# design.net
KiCad netlist of a schematic drawn in Altium Designer
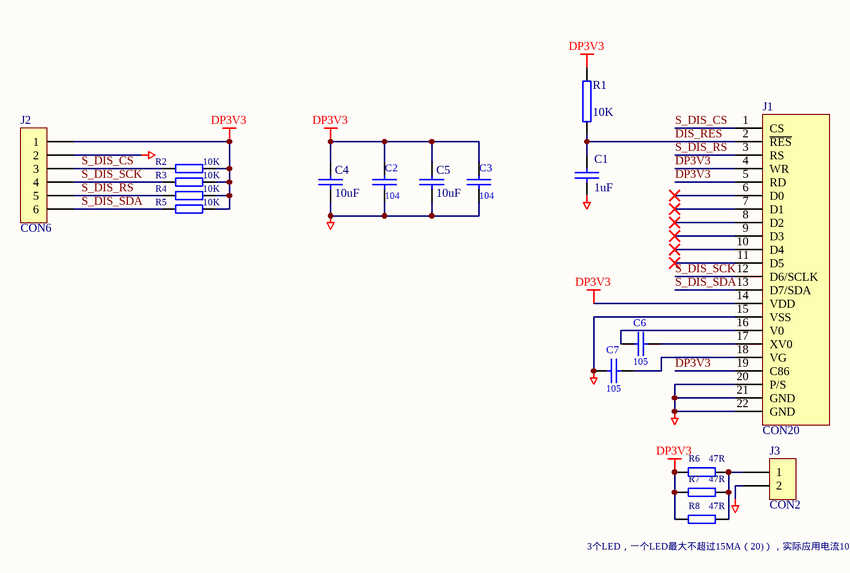
[diagram p0: 迷你随车充液晶显示板.SchDoc]

(export (version "E")
  (design (tool "Eeschema 10.0.6"))
  (components
    (comp (ref "C1")
      (value "1uF")
      (footprint "0603C")
      (description "0603贴片电容/50V/0.1uF/±10%/X7R")
      (libsource (lib "*") (part "CAP1"))
    )
    (comp (ref "C2")
      (value "104")
      (footprint "0603C")
      (description "Capacitor")
      (libsource (lib "*") (part "CAP"))
    )
    (comp (ref "C3")
      (value "104")
      (footprint "0603C")
      (description "Capacitor")
      (libsource (lib "*") (part "CAP"))
    )
    (comp (ref "C4") (value "10uF") (footprint "0805C") (libsource (lib "*") (part "CAP1")))
    (comp (ref "C5") (value "10uF") (footprint "0805C") (libsource (lib "*") (part "CAP1")))
    (comp (ref "C6")
      (value "105")
      (footprint "0603C")
      (description "Capacitor")
      (libsource (lib "*") (part "CAP"))
    )
    (comp (ref "C7")
      (value "105")
      (footprint "0603C")
      (description "Capacitor")
      (libsource (lib "*") (part "CAP"))
    )
    (comp (ref "J1")
      (value "CON20")
      (footprint "FPC20-0.5mm")
      (description "Connector")
      (libsource (lib "SCH") (part "CON20"))
    )
    (comp (ref "J2")
      (value "CON6")
      (footprint "CON06_2.54")
      (description "Connector")
      (libsource (lib "*") (part "CON6"))
    )
    (comp (ref "J3")
      (value "CON2")
      (footprint "JXL12864G-1504")
      (description "Connector")
      (libsource (lib "SCH") (part "CON2"))
    )
    (comp (ref "R1")
      (value "10K")
      (footprint "0603R")
      (description "0603贴片电阻/10K/0.1W/±5%")
      (libsource (lib "*") (part "RES1"))
    )
    (comp (ref "R2")
      (value "10K")
      (footprint "0603R")
      (description "RES")
      (libsource (lib "*") (part "RES-1"))
    )
    (comp (ref "R3")
      (value "10K")
      (footprint "0603R")
      (description "RES")
      (libsource (lib "*") (part "RES-1"))
    )
    (comp (ref "R4")
      (value "10K")
      (footprint "0603R")
      (description "RES")
      (libsource (lib "*") (part "RES-1"))
    )
    (comp (ref "R5")
      (value "10K")
      (footprint "0603R")
      (description "RES")
      (libsource (lib "*") (part "RES-1"))
    )
    (comp (ref "R6")
      (value "47R")
      (footprint "0603R")
      (description "RES")
      (libsource (lib "*") (part "RES-1"))
    )
    (comp (ref "R7")
      (value "47R")
      (footprint "0603R")
      (description "RES")
      (libsource (lib "*") (part "RES-1"))
    )
    (comp (ref "R8")
      (value "47R")
      (footprint "0603R")
      (description "RES")
      (libsource (lib "*") (part "RES-1"))
    )
  )
  (nets
    (net (code "1") (name "/DIS_RES") (class "Default")
      (node (ref "C1") (pin "2") (pinfunction "2_2") (pintype "passive"))
      (node (ref "J1") (pin "2") (pinfunction "~{RES}_2") (pintype "passive"))
      (node (ref "R1") (pin "2") (pinfunction "2_2") (pintype "passive"))
    )
    (net (code "2") (name "/S_DIS_CS") (class "Default")
      (node (ref "J1") (pin "1") (pinfunction "CS_1") (pintype "passive"))
      (node (ref "J2") (pin "3") (pinfunction "3_3") (pintype "passive"))
      (node (ref "R2") (pin "1") (pintype "passive"))
    )
    (net (code "3") (name "/S_DIS_RS") (class "Default")
      (node (ref "J1") (pin "3") (pinfunction "RS_3") (pintype "passive"))
      (node (ref "J2") (pin "5") (pinfunction "5_5") (pintype "passive"))
      (node (ref "R4") (pin "1") (pintype "passive"))
    )
    (net (code "4") (name "/S_DIS_SCK") (class "Default")
      (node (ref "J1") (pin "12") (pinfunction "D6/SCLK_12") (pintype "passive"))
      (node (ref "J2") (pin "4") (pinfunction "4_4") (pintype "passive"))
      (node (ref "R3") (pin "1") (pintype "passive"))
    )
    (net (code "5") (name "/S_DIS_SDA") (class "Default")
      (node (ref "J1") (pin "13") (pinfunction "D7/SDA_13") (pintype "passive"))
      (node (ref "J2") (pin "6") (pinfunction "6_6") (pintype "passive"))
      (node (ref "R5") (pin "1") (pintype "passive"))
    )
    (net (code "6") (name "DGND") (class "Default")
      (node (ref "C1") (pin "1") (pinfunction "1_1") (pintype "passive"))
      (node (ref "C2") (pin "1") (pintype "passive"))
      (node (ref "C3") (pin "1") (pintype "passive"))
      (node (ref "C4") (pin "2") (pinfunction "2_2") (pintype "passive"))
      (node (ref "C5") (pin "2") (pinfunction "2_2") (pintype "passive"))
      (node (ref "C7") (pin "2") (pintype "passive"))
      (node (ref "J1") (pin "15") (pinfunction "VSS_15") (pintype "passive"))
      (node (ref "J1") (pin "20") (pinfunction "P/S_20") (pintype "passive"))
      (node (ref "J1") (pin "21") (pinfunction "GND_21") (pintype "passive"))
      (node (ref "J1") (pin "22") (pinfunction "GND_22") (pintype "passive"))
      (node (ref "J2") (pin "2") (pinfunction "2_2") (pintype "passive"))
      (node (ref "J3") (pin "2") (pinfunction "2_2") (pintype "passive"))
    )
    (net (code "7") (name "DP3V3") (class "Default")
      (node (ref "C2") (pin "2") (pintype "passive"))
      (node (ref "C3") (pin "2") (pintype "passive"))
      (node (ref "C4") (pin "1") (pinfunction "1_1") (pintype "passive"))
      (node (ref "C5") (pin "1") (pinfunction "1_1") (pintype "passive"))
      (node (ref "J1") (pin "14") (pinfunction "VDD_14") (pintype "passive"))
      (node (ref "J1") (pin "19") (pinfunction "C86_19") (pintype "passive"))
      (node (ref "J1") (pin "4") (pinfunction "WR_4") (pintype "passive"))
      (node (ref "J1") (pin "5") (pinfunction "RD_5") (pintype "passive"))
      (node (ref "J2") (pin "1") (pinfunction "1_1") (pintype "passive"))
      (node (ref "R1") (pin "1") (pinfunction "1_1") (pintype "passive"))
      (node (ref "R2") (pin "2") (pintype "passive"))
      (node (ref "R3") (pin "2") (pintype "passive"))
      (node (ref "R4") (pin "2") (pintype "passive"))
      (node (ref "R5") (pin "2") (pintype "passive"))
      (node (ref "R6") (pin "1") (pintype "passive"))
      (node (ref "R7") (pin "1") (pintype "passive"))
      (node (ref "R8") (pin "1") (pintype "passive"))
    )
    (net (code "8") (name "Net-(J1-V0)") (class "Default")
      (node (ref "C6") (pin "2") (pintype "passive"))
      (node (ref "J1") (pin "16") (pinfunction "V0_16") (pintype "passive"))
    )
    (net (code "9") (name "Net-(J1-VG)") (class "Default")
      (node (ref "C7") (pin "1") (pintype "passive"))
      (node (ref "J1") (pin "18") (pinfunction "VG_18") (pintype "passive"))
    )
    (net (code "10") (name "Net-(J1-XV0)") (class "Default")
      (node (ref "C6") (pin "1") (pintype "passive"))
      (node (ref "J1") (pin "17") (pinfunction "XV0_17") (pintype "passive"))
    )
    (net (code "11") (name "Net-(J3-Pad1)") (class "Default")
      (node (ref "J3") (pin "1") (pinfunction "1_1") (pintype "passive"))
      (node (ref "R6") (pin "2") (pintype "passive"))
      (node (ref "R7") (pin "2") (pintype "passive"))
      (node (ref "R8") (pin "2") (pintype "passive"))
    )
    (net (code "12") (name "unconnected-(J1-D0-Pad6)") (class "Default")
      (node (ref "J1") (pin "6") (pinfunction "D0_6") (pintype "passive+no_connect"))
    )
    (net (code "13") (name "unconnected-(J1-D1-Pad7)") (class "Default")
      (node (ref "J1") (pin "7") (pinfunction "D1_7") (pintype "passive+no_connect"))
    )
    (net (code "14") (name "unconnected-(J1-D2-Pad8)") (class "Default")
      (node (ref "J1") (pin "8") (pinfunction "D2_8") (pintype "passive+no_connect"))
    )
    (net (code "15") (name "unconnected-(J1-D3-Pad9)") (class "Default")
      (node (ref "J1") (pin "9") (pinfunction "D3_9") (pintype "passive+no_connect"))
    )
    (net (code "16") (name "unconnected-(J1-D4-Pad10)") (class "Default")
      (node (ref "J1") (pin "10") (pinfunction "D4_10") (pintype "passive+no_connect"))
    )
    (net (code "17") (name "unconnected-(J1-D5-Pad11)") (class "Default")
      (node (ref "J1") (pin "11") (pinfunction "D5_11") (pintype "passive+no_connect"))
    )
  )
)
